# PRINT.net
KiCad netlist of a schematic drawn in EAGLE
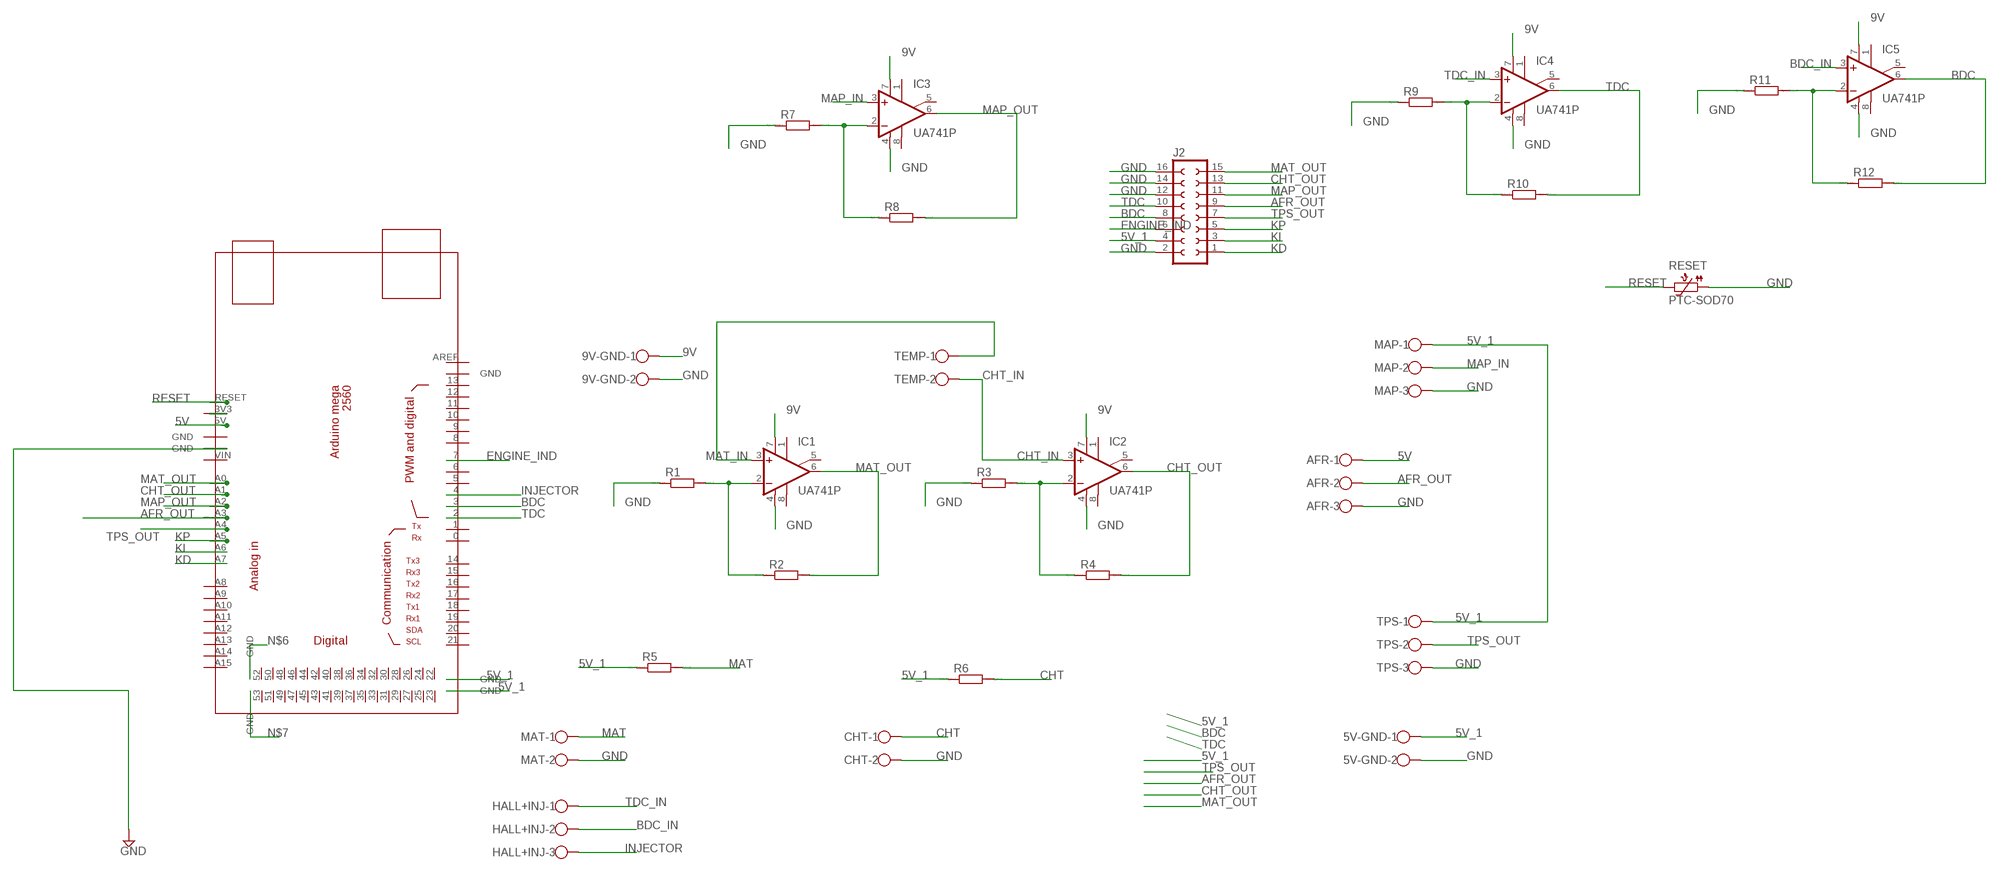
[diagram p0: schematic, sheet 1]

(export (version "E")
  (design (tool "Eeschema 10.0.6"))
  (components
    (comp (ref "5V-GND")
      (value "W237-102")
      (footprint "eagle-import:W237-102")
      (fields (field (name "MPN") "237-102"))
      (libsource (lib "eagle-import") (part "W237-102"))
    )
    (comp (ref "9V-GND")
      (value "W237-102")
      (footprint "eagle-import:W237-102")
      (fields (field (name "MPN") "237-102"))
      (libsource (lib "eagle-import") (part "W237-102"))
    )
    (comp (ref "AFR")
      (value "W237-103")
      (footprint "eagle-import:W237-103")
      (fields (field (name "MPN") "237-103"))
      (libsource (lib "eagle-import") (part "con-wago-500_195_W237-103"))
    )
    (comp (ref "CHT")
      (value "W237-102")
      (footprint "eagle-import:W237-102")
      (fields (field (name "MPN") "237-102"))
      (libsource (lib "eagle-import") (part "W237-102"))
    )
    (comp (ref "HALL+INJ")
      (value "W237-103")
      (footprint "eagle-import:W237-103")
      (fields (field (name "MPN") "237-103"))
      (libsource (lib "eagle-import") (part "W237-103"))
    )
    (comp (ref "IC1")
      (value "UA741P")
      (footprint "eagle-import:DIL08")
      (libsource (lib "eagle-import") (part "741PUA"))
    )
    (comp (ref "IC2")
      (value "UA741P")
      (footprint "eagle-import:DIL08")
      (libsource (lib "eagle-import") (part "741PUA"))
    )
    (comp (ref "IC3")
      (value "UA741P")
      (footprint "eagle-import:DIL08")
      (libsource (lib "eagle-import") (part "741PUA"))
    )
    (comp (ref "IC4")
      (value "UA741P")
      (footprint "eagle-import:DIL08")
      (libsource (lib "eagle-import") (part "741PUA"))
    )
    (comp (ref "IC5")
      (value "UA741P")
      (footprint "eagle-import:DIL08")
      (libsource (lib "eagle-import") (part "741PUA"))
    )
    (comp (ref "J2")
      (value "SOCKET-16V")
      (footprint "eagle-import:S16V")
      (libsource (lib "eagle-import") (part "SOCKET-16V"))
    )
    (comp (ref "MAP")
      (value "W237-103")
      (footprint "eagle-import:W237-103")
      (fields (field (name "MPN") "237-103"))
      (libsource (lib "eagle-import") (part "W237-103"))
    )
    (comp (ref "MAT")
      (value "W237-102")
      (footprint "eagle-import:W237-102")
      (fields (field (name "MPN") "237-102"))
      (libsource (lib "eagle-import") (part "W237-102"))
    )
    (comp (ref "R1")
      (value "R0204/7")
      (footprint "eagle-import:0204_7")
      (libsource (lib "eagle-import") (part "R0204/7"))
    )
    (comp (ref "R2")
      (value "R0204/7")
      (footprint "eagle-import:0204_7")
      (libsource (lib "eagle-import") (part "R0204/7"))
    )
    (comp (ref "R3")
      (value "R0204/7")
      (footprint "eagle-import:0204_7")
      (libsource (lib "eagle-import") (part "R0204/7"))
    )
    (comp (ref "R4")
      (value "R0204/7")
      (footprint "eagle-import:0204_7")
      (libsource (lib "eagle-import") (part "R0204/7"))
    )
    (comp (ref "R5")
      (value "R0204/7")
      (footprint "eagle-import:0204_7")
      (libsource (lib "eagle-import") (part "R0204/7"))
    )
    (comp (ref "R6")
      (value "R0204/7")
      (footprint "eagle-import:0204_7")
      (libsource (lib "eagle-import") (part "R0204/7"))
    )
    (comp (ref "R7")
      (value "R0204/7")
      (footprint "eagle-import:0204_7")
      (libsource (lib "eagle-import") (part "R0204/7"))
    )
    (comp (ref "R8")
      (value "R0204/7")
      (footprint "eagle-import:0204_7")
      (libsource (lib "eagle-import") (part "R0204/7"))
    )
    (comp (ref "R9")
      (value "R0204/7")
      (footprint "eagle-import:0204_7")
      (libsource (lib "eagle-import") (part "R0204/7"))
    )
    (comp (ref "R10")
      (value "R0204/7")
      (footprint "eagle-import:0204_7")
      (libsource (lib "eagle-import") (part "R0204/7"))
    )
    (comp (ref "R11")
      (value "R0204/7")
      (footprint "eagle-import:0204_7")
      (libsource (lib "eagle-import") (part "R0204/7"))
    )
    (comp (ref "R12")
      (value "R0204/7")
      (footprint "eagle-import:0204_7")
      (libsource (lib "eagle-import") (part "R0204/7"))
    )
    (comp (ref "RESET")
      (value "PTC-SOD70")
      (footprint "eagle-import:SOD70")
      (libsource (lib "eagle-import") (part "PTC-SOD70"))
    )
    (comp (ref "TEMP")
      (value "W237-102")
      (footprint "eagle-import:W237-102")
      (fields (field (name "MPN") "237-102"))
      (libsource (lib "eagle-import") (part "W237-102"))
    )
    (comp (ref "TPS")
      (value "W237-103")
      (footprint "eagle-import:W237-103")
      (fields (field (name "MPN") "237-103"))
      (libsource (lib "eagle-import") (part "W237-103"))
    )
    (comp (ref "U$1")
      (value "MEGA_DEVICE")
      (footprint "eagle-import:MEGAOUTLINE")
      (libsource (lib "eagle-import") (part "MEGA_DEVICE"))
    )
  )
  (nets
    (net (code "1") (name "/5V") (class "Default")
      (node (ref "AFR") (pin "1") (pinfunction "KL_1") (pintype "passive"))
      (node (ref "U$1") (pin "5V") (pinfunction "5V_5V") (pintype "bidirectional"))
    )
    (net (code "2") (name "/5V_1") (class "Default")
      (node (ref "5V-GND") (pin "1") (pinfunction "KL_1") (pintype "passive"))
      (node (ref "J2") (pin "4") (pinfunction "4_4") (pintype "passive"))
      (node (ref "MAP") (pin "1") (pinfunction "KL_1") (pintype "passive"))
      (node (ref "R5") (pin "1") (pinfunction "1_1") (pintype "passive"))
      (node (ref "R6") (pin "1") (pinfunction "1_1") (pintype "passive"))
      (node (ref "TPS") (pin "1") (pinfunction "KL_1") (pintype "passive"))
      (node (ref "U$1") (pin "GND@4") (pinfunction "GND_GND@4") (pintype "bidirectional"))
      (node (ref "U$1") (pin "GND@5") (pinfunction "GND_GND@5") (pintype "bidirectional"))
    )
    (net (code "3") (name "/9V") (class "Default")
      (node (ref "9V-GND") (pin "1") (pinfunction "KL_1") (pintype "passive"))
      (node (ref "IC1") (pin "7") (pinfunction "V+_7") (pintype "power_in"))
      (node (ref "IC2") (pin "7") (pinfunction "V+_7") (pintype "power_in"))
      (node (ref "IC3") (pin "7") (pinfunction "V+_7") (pintype "power_in"))
      (node (ref "IC4") (pin "7") (pinfunction "V+_7") (pintype "power_in"))
      (node (ref "IC5") (pin "7") (pinfunction "V+_7") (pintype "power_in"))
    )
    (net (code "4") (name "/AFR_OUT") (class "Default")
      (node (ref "AFR") (pin "2") (pinfunction "KL_2") (pintype "passive"))
      (node (ref "J2") (pin "9") (pinfunction "9_9") (pintype "passive"))
      (node (ref "U$1") (pin "A3") (pinfunction "A3_A3") (pintype "bidirectional"))
    )
    (net (code "5") (name "/BDC") (class "Default")
      (node (ref "IC5") (pin "6") (pinfunction "OUT_6") (pintype "output"))
      (node (ref "J2") (pin "8") (pinfunction "8_8") (pintype "passive"))
      (node (ref "R12") (pin "2") (pinfunction "2_2") (pintype "passive"))
      (node (ref "U$1") (pin "3") (pinfunction "3_3") (pintype "bidirectional"))
    )
    (net (code "6") (name "/BDC_IN") (class "Default")
      (node (ref "HALL+INJ") (pin "2") (pinfunction "KL_2") (pintype "passive"))
      (node (ref "IC5") (pin "3") (pinfunction "+IN_3") (pintype "input"))
    )
    (net (code "7") (name "/CHT") (class "Default")
      (node (ref "CHT") (pin "1") (pinfunction "KL_1") (pintype "passive"))
      (node (ref "R6") (pin "2") (pinfunction "2_2") (pintype "passive"))
    )
    (net (code "8") (name "/CHT_IN") (class "Default")
      (node (ref "IC2") (pin "3") (pinfunction "+IN_3") (pintype "input"))
      (node (ref "TEMP") (pin "2") (pinfunction "KL_2") (pintype "passive"))
    )
    (net (code "9") (name "/CHT_OUT") (class "Default")
      (node (ref "IC2") (pin "6") (pinfunction "OUT_6") (pintype "output"))
      (node (ref "J2") (pin "13") (pinfunction "13_13") (pintype "passive"))
      (node (ref "R4") (pin "2") (pinfunction "2_2") (pintype "passive"))
      (node (ref "U$1") (pin "A1") (pinfunction "A1_A1") (pintype "bidirectional"))
    )
    (net (code "10") (name "/ENGINE_IND") (class "Default")
      (node (ref "J2") (pin "6") (pinfunction "6_6") (pintype "passive"))
      (node (ref "U$1") (pin "7") (pinfunction "7_7") (pintype "bidirectional"))
    )
    (net (code "11") (name "/INJECTOR") (class "Default")
      (node (ref "HALL+INJ") (pin "3") (pinfunction "KL_3") (pintype "passive"))
      (node (ref "U$1") (pin "4") (pinfunction "4_4") (pintype "bidirectional"))
    )
    (net (code "12") (name "/KD") (class "Default")
      (node (ref "J2") (pin "1") (pinfunction "1_1") (pintype "passive"))
      (node (ref "U$1") (pin "A7") (pinfunction "A7_A7") (pintype "bidirectional"))
    )
    (net (code "13") (name "/KI") (class "Default")
      (node (ref "J2") (pin "3") (pinfunction "3_3") (pintype "passive"))
      (node (ref "U$1") (pin "A6") (pinfunction "A6_A6") (pintype "bidirectional"))
    )
    (net (code "14") (name "/KP") (class "Default")
      (node (ref "J2") (pin "5") (pinfunction "5_5") (pintype "passive"))
      (node (ref "U$1") (pin "A5") (pinfunction "A5_A5") (pintype "bidirectional"))
    )
    (net (code "15") (name "/MAP_IN") (class "Default")
      (node (ref "IC3") (pin "3") (pinfunction "+IN_3") (pintype "input"))
      (node (ref "MAP") (pin "2") (pinfunction "KL_2") (pintype "passive"))
    )
    (net (code "16") (name "/MAP_OUT") (class "Default")
      (node (ref "IC3") (pin "6") (pinfunction "OUT_6") (pintype "output"))
      (node (ref "J2") (pin "11") (pinfunction "11_11") (pintype "passive"))
      (node (ref "R8") (pin "2") (pinfunction "2_2") (pintype "passive"))
      (node (ref "U$1") (pin "A2") (pinfunction "A2_A2") (pintype "bidirectional"))
    )
    (net (code "17") (name "/MAT") (class "Default")
      (node (ref "MAT") (pin "1") (pinfunction "KL_1") (pintype "passive"))
      (node (ref "R5") (pin "2") (pinfunction "2_2") (pintype "passive"))
    )
    (net (code "18") (name "/MAT_IN") (class "Default")
      (node (ref "IC1") (pin "3") (pinfunction "+IN_3") (pintype "input"))
      (node (ref "TEMP") (pin "1") (pinfunction "KL_1") (pintype "passive"))
    )
    (net (code "19") (name "/MAT_OUT") (class "Default")
      (node (ref "IC1") (pin "6") (pinfunction "OUT_6") (pintype "output"))
      (node (ref "J2") (pin "15") (pinfunction "15_15") (pintype "passive"))
      (node (ref "R2") (pin "2") (pinfunction "2_2") (pintype "passive"))
      (node (ref "U$1") (pin "A0") (pinfunction "A0_A0") (pintype "bidirectional"))
    )
    (net (code "20") (name "/N$6") (class "Default")
      (node (ref "U$1") (pin "GND@6") (pinfunction "GND_GND@6") (pintype "bidirectional"))
    )
    (net (code "21") (name "/N$7") (class "Default")
      (node (ref "U$1") (pin "GND@7") (pinfunction "GND_GND@7") (pintype "bidirectional"))
    )
    (net (code "22") (name "/RESET") (class "Default")
      (node (ref "RESET") (pin "2") (pinfunction "2_2") (pintype "passive"))
      (node (ref "U$1") (pin "RESET") (pinfunction "RESET_RESET") (pintype "bidirectional"))
    )
    (net (code "23") (name "/TDC") (class "Default")
      (node (ref "IC4") (pin "6") (pinfunction "OUT_6") (pintype "output"))
      (node (ref "J2") (pin "10") (pinfunction "10_10") (pintype "passive"))
      (node (ref "R10") (pin "2") (pinfunction "2_2") (pintype "passive"))
      (node (ref "U$1") (pin "2") (pinfunction "2_2") (pintype "bidirectional"))
    )
    (net (code "24") (name "/TDC_IN") (class "Default")
      (node (ref "HALL+INJ") (pin "1") (pinfunction "KL_1") (pintype "passive"))
      (node (ref "IC4") (pin "3") (pinfunction "+IN_3") (pintype "input"))
    )
    (net (code "25") (name "/TPS_OUT") (class "Default")
      (node (ref "J2") (pin "7") (pinfunction "7_7") (pintype "passive"))
      (node (ref "TPS") (pin "2") (pinfunction "KL_2") (pintype "passive"))
      (node (ref "U$1") (pin "A4") (pinfunction "A4_A4") (pintype "bidirectional"))
    )
    (net (code "26") (name "GND") (class "Default")
      (node (ref "5V-GND") (pin "2") (pinfunction "KL_2") (pintype "passive"))
      (node (ref "9V-GND") (pin "2") (pinfunction "KL_2") (pintype "passive"))
      (node (ref "AFR") (pin "3") (pinfunction "KL_3") (pintype "passive"))
      (node (ref "CHT") (pin "2") (pinfunction "KL_2") (pintype "passive"))
      (node (ref "IC1") (pin "4") (pinfunction "V-_4") (pintype "power_in"))
      (node (ref "IC2") (pin "4") (pinfunction "V-_4") (pintype "power_in"))
      (node (ref "IC3") (pin "4") (pinfunction "V-_4") (pintype "power_in"))
      (node (ref "IC4") (pin "4") (pinfunction "V-_4") (pintype "power_in"))
      (node (ref "IC5") (pin "4") (pinfunction "V-_4") (pintype "power_in"))
      (node (ref "J2") (pin "12") (pinfunction "12_12") (pintype "passive"))
      (node (ref "J2") (pin "14") (pinfunction "14_14") (pintype "passive"))
      (node (ref "J2") (pin "16") (pinfunction "16_16") (pintype "passive"))
      (node (ref "J2") (pin "2") (pinfunction "2_2") (pintype "passive"))
      (node (ref "MAP") (pin "3") (pinfunction "KL_3") (pintype "passive"))
      (node (ref "MAT") (pin "2") (pinfunction "KL_2") (pintype "passive"))
      (node (ref "R1") (pin "1") (pinfunction "1_1") (pintype "passive"))
      (node (ref "R11") (pin "1") (pinfunction "1_1") (pintype "passive"))
      (node (ref "R3") (pin "1") (pinfunction "1_1") (pintype "passive"))
      (node (ref "R7") (pin "1") (pinfunction "1_1") (pintype "passive"))
      (node (ref "R9") (pin "1") (pinfunction "1_1") (pintype "passive"))
      (node (ref "RESET") (pin "1") (pinfunction "1_1") (pintype "passive"))
      (node (ref "TPS") (pin "3") (pinfunction "KL_3") (pintype "passive"))
      (node (ref "U$1") (pin "GND@3") (pinfunction "GND_GND@3") (pintype "bidirectional"))
    )
    (net (code "27") (name "Net-(IC1--IN)") (class "Default")
      (node (ref "IC1") (pin "2") (pinfunction "-IN_2") (pintype "input"))
      (node (ref "R1") (pin "2") (pinfunction "2_2") (pintype "passive"))
      (node (ref "R2") (pin "1") (pinfunction "1_1") (pintype "passive"))
    )
    (net (code "28") (name "Net-(IC2--IN)") (class "Default")
      (node (ref "IC2") (pin "2") (pinfunction "-IN_2") (pintype "input"))
      (node (ref "R3") (pin "2") (pinfunction "2_2") (pintype "passive"))
      (node (ref "R4") (pin "1") (pinfunction "1_1") (pintype "passive"))
    )
    (net (code "29") (name "Net-(IC3--IN)") (class "Default")
      (node (ref "IC3") (pin "2") (pinfunction "-IN_2") (pintype "input"))
      (node (ref "R7") (pin "2") (pinfunction "2_2") (pintype "passive"))
      (node (ref "R8") (pin "1") (pinfunction "1_1") (pintype "passive"))
    )
    (net (code "30") (name "Net-(IC4--IN)") (class "Default")
      (node (ref "IC4") (pin "2") (pinfunction "-IN_2") (pintype "input"))
      (node (ref "R10") (pin "1") (pinfunction "1_1") (pintype "passive"))
      (node (ref "R9") (pin "2") (pinfunction "2_2") (pintype "passive"))
    )
    (net (code "31") (name "Net-(IC5--IN)") (class "Default")
      (node (ref "IC5") (pin "2") (pinfunction "-IN_2") (pintype "input"))
      (node (ref "R11") (pin "2") (pinfunction "2_2") (pintype "passive"))
      (node (ref "R12") (pin "1") (pinfunction "1_1") (pintype "passive"))
    )
    (net (code "32") (name "unconnected-(IC1-ON1-Pad1)") (class "Default")
      (node (ref "IC1") (pin "1") (pinfunction "ON1_1") (pintype "passive"))
    )
    (net (code "33") (name "unconnected-(IC1-ON2-Pad5)") (class "Default")
      (node (ref "IC1") (pin "5") (pinfunction "ON2_5") (pintype "passive"))
    )
    (net (code "34") (name "unconnected-(IC1-OPT-Pad8)") (class "Default")
      (node (ref "IC1") (pin "8") (pinfunction "OPT_8") (pintype "passive"))
    )
    (net (code "35") (name "unconnected-(IC2-ON1-Pad1)") (class "Default")
      (node (ref "IC2") (pin "1") (pinfunction "ON1_1") (pintype "passive"))
    )
    (net (code "36") (name "unconnected-(IC2-ON2-Pad5)") (class "Default")
      (node (ref "IC2") (pin "5") (pinfunction "ON2_5") (pintype "passive"))
    )
    (net (code "37") (name "unconnected-(IC2-OPT-Pad8)") (class "Default")
      (node (ref "IC2") (pin "8") (pinfunction "OPT_8") (pintype "passive"))
    )
    (net (code "38") (name "unconnected-(IC3-ON1-Pad1)") (class "Default")
      (node (ref "IC3") (pin "1") (pinfunction "ON1_1") (pintype "passive"))
    )
    (net (code "39") (name "unconnected-(IC3-ON2-Pad5)") (class "Default")
      (node (ref "IC3") (pin "5") (pinfunction "ON2_5") (pintype "passive"))
    )
    (net (code "40") (name "unconnected-(IC3-OPT-Pad8)") (class "Default")
      (node (ref "IC3") (pin "8") (pinfunction "OPT_8") (pintype "passive"))
    )
    (net (code "41") (name "unconnected-(IC4-ON1-Pad1)") (class "Default")
      (node (ref "IC4") (pin "1") (pinfunction "ON1_1") (pintype "passive"))
    )
    (net (code "42") (name "unconnected-(IC4-ON2-Pad5)") (class "Default")
      (node (ref "IC4") (pin "5") (pinfunction "ON2_5") (pintype "passive"))
    )
    (net (code "43") (name "unconnected-(IC4-OPT-Pad8)") (class "Default")
      (node (ref "IC4") (pin "8") (pinfunction "OPT_8") (pintype "passive"))
    )
    (net (code "44") (name "unconnected-(IC5-ON1-Pad1)") (class "Default")
      (node (ref "IC5") (pin "1") (pinfunction "ON1_1") (pintype "passive"))
    )
    (net (code "45") (name "unconnected-(IC5-ON2-Pad5)") (class "Default")
      (node (ref "IC5") (pin "5") (pinfunction "ON2_5") (pintype "passive"))
    )
    (net (code "46") (name "unconnected-(IC5-OPT-Pad8)") (class "Default")
      (node (ref "IC5") (pin "8") (pinfunction "OPT_8") (pintype "passive"))
    )
    (net (code "47") (name "unconnected-(U$1-GND-PadGND@1)") (class "Default")
      (node (ref "U$1") (pin "GND@1") (pinfunction "GND_GND@1") (pintype "bidirectional"))
    )
    (net (code "48") (name "unconnected-(U$1-GND-PadGND@2)") (class "Default")
      (node (ref "U$1") (pin "GND@2") (pinfunction "GND_GND@2") (pintype "bidirectional"))
    )
    (net (code "49") (name "unconnected-(U$1-Pad0)") (class "Default")
      (node (ref "U$1") (pin "0") (pinfunction "0_0") (pintype "bidirectional"))
    )
    (net (code "50") (name "unconnected-(U$1-Pad1)") (class "Default")
      (node (ref "U$1") (pin "1") (pinfunction "1_1") (pintype "bidirectional"))
    )
    (net (code "51") (name "unconnected-(U$1-Pad3V3)") (class "Default")
      (node (ref "U$1") (pin "3V3") (pinfunction "3V3_3V3") (pintype "bidirectional"))
    )
    (net (code "52") (name "unconnected-(U$1-Pad5)") (class "Default")
      (node (ref "U$1") (pin "5") (pinfunction "5_5") (pintype "bidirectional"))
    )
    (net (code "53") (name "unconnected-(U$1-Pad6)") (class "Default")
      (node (ref "U$1") (pin "6") (pinfunction "6_6") (pintype "bidirectional"))
    )
    (net (code "54") (name "unconnected-(U$1-Pad8)") (class "Default")
      (node (ref "U$1") (pin "8") (pinfunction "8_8") (pintype "bidirectional"))
    )
    (net (code "55") (name "unconnected-(U$1-Pad9)") (class "Default")
      (node (ref "U$1") (pin "9") (pinfunction "9_9") (pintype "bidirectional"))
    )
    (net (code "56") (name "unconnected-(U$1-Pad10)") (class "Default")
      (node (ref "U$1") (pin "10") (pinfunction "10_10") (pintype "bidirectional"))
    )
    (net (code "57") (name "unconnected-(U$1-Pad11)") (class "Default")
      (node (ref "U$1") (pin "11") (pinfunction "11_11") (pintype "bidirectional"))
    )
    (net (code "58") (name "unconnected-(U$1-Pad12)") (class "Default")
      (node (ref "U$1") (pin "12") (pinfunction "12_12") (pintype "bidirectional"))
    )
    (net (code "59") (name "unconnected-(U$1-Pad13)") (class "Default")
      (node (ref "U$1") (pin "13") (pinfunction "13_13") (pintype "bidirectional"))
    )
    (net (code "60") (name "unconnected-(U$1-Pad14)") (class "Default")
      (node (ref "U$1") (pin "14") (pinfunction "14_14") (pintype "bidirectional"))
    )
    (net (code "61") (name "unconnected-(U$1-Pad15)") (class "Default")
      (node (ref "U$1") (pin "15") (pinfunction "15_15") (pintype "bidirectional"))
    )
    (net (code "62") (name "unconnected-(U$1-Pad16)") (class "Default")
      (node (ref "U$1") (pin "16") (pinfunction "16_16") (pintype "bidirectional"))
    )
    (net (code "63") (name "unconnected-(U$1-Pad17)") (class "Default")
      (node (ref "U$1") (pin "17") (pinfunction "17_17") (pintype "bidirectional"))
    )
    (net (code "64") (name "unconnected-(U$1-Pad18)") (class "Default")
      (node (ref "U$1") (pin "18") (pinfunction "18_18") (pintype "bidirectional"))
    )
    (net (code "65") (name "unconnected-(U$1-Pad19)") (class "Default")
      (node (ref "U$1") (pin "19") (pinfunction "19_19") (pintype "bidirectional"))
    )
    (net (code "66") (name "unconnected-(U$1-Pad20)") (class "Default")
      (node (ref "U$1") (pin "20") (pinfunction "20_20") (pintype "bidirectional"))
    )
    (net (code "67") (name "unconnected-(U$1-Pad21)") (class "Default")
      (node (ref "U$1") (pin "21") (pinfunction "21_21") (pintype "bidirectional"))
    )
    (net (code "68") (name "unconnected-(U$1-Pad22)") (class "Default")
      (node (ref "U$1") (pin "22") (pinfunction "22_22") (pintype "bidirectional"))
    )
    (net (code "69") (name "unconnected-(U$1-Pad23)") (class "Default")
      (node (ref "U$1") (pin "23") (pinfunction "23_23") (pintype "bidirectional"))
    )
    (net (code "70") (name "unconnected-(U$1-Pad24)") (class "Default")
      (node (ref "U$1") (pin "24") (pinfunction "24_24") (pintype "bidirectional"))
    )
    (net (code "71") (name "unconnected-(U$1-Pad25)") (class "Default")
      (node (ref "U$1") (pin "25") (pinfunction "25_25") (pintype "bidirectional"))
    )
    (net (code "72") (name "unconnected-(U$1-Pad26)") (class "Default")
      (node (ref "U$1") (pin "26") (pinfunction "26_26") (pintype "bidirectional"))
    )
    (net (code "73") (name "unconnected-(U$1-Pad27)") (class "Default")
      (node (ref "U$1") (pin "27") (pinfunction "27_27") (pintype "bidirectional"))
    )
    (net (code "74") (name "unconnected-(U$1-Pad28)") (class "Default")
      (node (ref "U$1") (pin "28") (pinfunction "28_28") (pintype "bidirectional"))
    )
    (net (code "75") (name "unconnected-(U$1-Pad29)") (class "Default")
      (node (ref "U$1") (pin "29") (pinfunction "29_29") (pintype "bidirectional"))
    )
    (net (code "76") (name "unconnected-(U$1-Pad30)") (class "Default")
      (node (ref "U$1") (pin "30") (pinfunction "30_30") (pintype "bidirectional"))
    )
    (net (code "77") (name "unconnected-(U$1-Pad31)") (class "Default")
      (node (ref "U$1") (pin "31") (pinfunction "31_31") (pintype "bidirectional"))
    )
    (net (code "78") (name "unconnected-(U$1-Pad32)") (class "Default")
      (node (ref "U$1") (pin "32") (pinfunction "32_32") (pintype "bidirectional"))
    )
    (net (code "79") (name "unconnected-(U$1-Pad33)") (class "Default")
      (node (ref "U$1") (pin "33") (pinfunction "33_33") (pintype "bidirectional"))
    )
    (net (code "80") (name "unconnected-(U$1-Pad34)") (class "Default")
      (node (ref "U$1") (pin "34") (pinfunction "34_34") (pintype "bidirectional"))
    )
    (net (code "81") (name "unconnected-(U$1-Pad35)") (class "Default")
      (node (ref "U$1") (pin "35") (pinfunction "35_35") (pintype "bidirectional"))
    )
    (net (code "82") (name "unconnected-(U$1-Pad36)") (class "Default")
      (node (ref "U$1") (pin "36") (pinfunction "36_36") (pintype "bidirectional"))
    )
    (net (code "83") (name "unconnected-(U$1-Pad37)") (class "Default")
      (node (ref "U$1") (pin "37") (pinfunction "37_37") (pintype "bidirectional"))
    )
    (net (code "84") (name "unconnected-(U$1-Pad38)") (class "Default")
      (node (ref "U$1") (pin "38") (pinfunction "38_38") (pintype "bidirectional"))
    )
    (net (code "85") (name "unconnected-(U$1-Pad39)") (class "Default")
      (node (ref "U$1") (pin "39") (pinfunction "39_39") (pintype "bidirectional"))
    )
    (net (code "86") (name "unconnected-(U$1-Pad40)") (class "Default")
      (node (ref "U$1") (pin "40") (pinfunction "40_40") (pintype "bidirectional"))
    )
    (net (code "87") (name "unconnected-(U$1-Pad41)") (class "Default")
      (node (ref "U$1") (pin "41") (pinfunction "41_41") (pintype "bidirectional"))
    )
    (net (code "88") (name "unconnected-(U$1-Pad42)") (class "Default")
      (node (ref "U$1") (pin "42") (pinfunction "42_42") (pintype "bidirectional"))
    )
    (net (code "89") (name "unconnected-(U$1-Pad43)") (class "Default")
      (node (ref "U$1") (pin "43") (pinfunction "43_43") (pintype "bidirectional"))
    )
    (net (code "90") (name "unconnected-(U$1-Pad44)") (class "Default")
      (node (ref "U$1") (pin "44") (pinfunction "44_44") (pintype "bidirectional"))
    )
    (net (code "91") (name "unconnected-(U$1-Pad45)") (class "Default")
      (node (ref "U$1") (pin "45") (pinfunction "45_45") (pintype "bidirectional"))
    )
    (net (code "92") (name "unconnected-(U$1-Pad46)") (class "Default")
      (node (ref "U$1") (pin "46") (pinfunction "46_46") (pintype "bidirectional"))
    )
    (net (code "93") (name "unconnected-(U$1-Pad47)") (class "Default")
      (node (ref "U$1") (pin "47") (pinfunction "47_47") (pintype "bidirectional"))
    )
    (net (code "94") (name "unconnected-(U$1-Pad48)") (class "Default")
      (node (ref "U$1") (pin "48") (pinfunction "48_48") (pintype "bidirectional"))
    )
    (net (code "95") (name "unconnected-(U$1-Pad49)") (class "Default")
      (node (ref "U$1") (pin "49") (pinfunction "49_49") (pintype "bidirectional"))
    )
    (net (code "96") (name "unconnected-(U$1-Pad50)") (class "Default")
      (node (ref "U$1") (pin "50") (pinfunction "50_50") (pintype "bidirectional"))
    )
    (net (code "97") (name "unconnected-(U$1-Pad51)") (class "Default")
      (node (ref "U$1") (pin "51") (pinfunction "51_51") (pintype "bidirectional"))
    )
    (net (code "98") (name "unconnected-(U$1-Pad52)") (class "Default")
      (node (ref "U$1") (pin "52") (pinfunction "52_52") (pintype "bidirectional"))
    )
    (net (code "99") (name "unconnected-(U$1-Pad53)") (class "Default")
      (node (ref "U$1") (pin "53") (pinfunction "53_53") (pintype "bidirectional"))
    )
    (net (code "100") (name "unconnected-(U$1-PadA8)") (class "Default")
      (node (ref "U$1") (pin "A8") (pinfunction "A8_A8") (pintype "bidirectional"))
    )
    (net (code "101") (name "unconnected-(U$1-PadA9)") (class "Default")
      (node (ref "U$1") (pin "A9") (pinfunction "A9_A9") (pintype "bidirectional"))
    )
    (net (code "102") (name "unconnected-(U$1-PadA10)") (class "Default")
      (node (ref "U$1") (pin "A10") (pinfunction "A10_A10") (pintype "bidirectional"))
    )
    (net (code "103") (name "unconnected-(U$1-PadA11)") (class "Default")
      (node (ref "U$1") (pin "A11") (pinfunction "A11_A11") (pintype "bidirectional"))
    )
    (net (code "104") (name "unconnected-(U$1-PadA12)") (class "Default")
      (node (ref "U$1") (pin "A12") (pinfunction "A12_A12") (pintype "bidirectional"))
    )
    (net (code "105") (name "unconnected-(U$1-PadA13)") (class "Default")
      (node (ref "U$1") (pin "A13") (pinfunction "A13_A13") (pintype "bidirectional"))
    )
    (net (code "106") (name "unconnected-(U$1-PadA14)") (class "Default")
      (node (ref "U$1") (pin "A14") (pinfunction "A14_A14") (pintype "bidirectional"))
    )
    (net (code "107") (name "unconnected-(U$1-PadA15)") (class "Default")
      (node (ref "U$1") (pin "A15") (pinfunction "A15_A15") (pintype "bidirectional"))
    )
    (net (code "108") (name "unconnected-(U$1-PadAREF)") (class "Default")
      (node (ref "U$1") (pin "AREF") (pinfunction "AREF_AREF") (pintype "bidirectional"))
    )
    (net (code "109") (name "unconnected-(U$1-PadVIN)") (class "Default")
      (node (ref "U$1") (pin "VIN") (pinfunction "VIN_VIN") (pintype "bidirectional"))
    )
  )
)
